# VCO_BFP420.net
KiCad netlist of a schematic drawn in Altium Designer
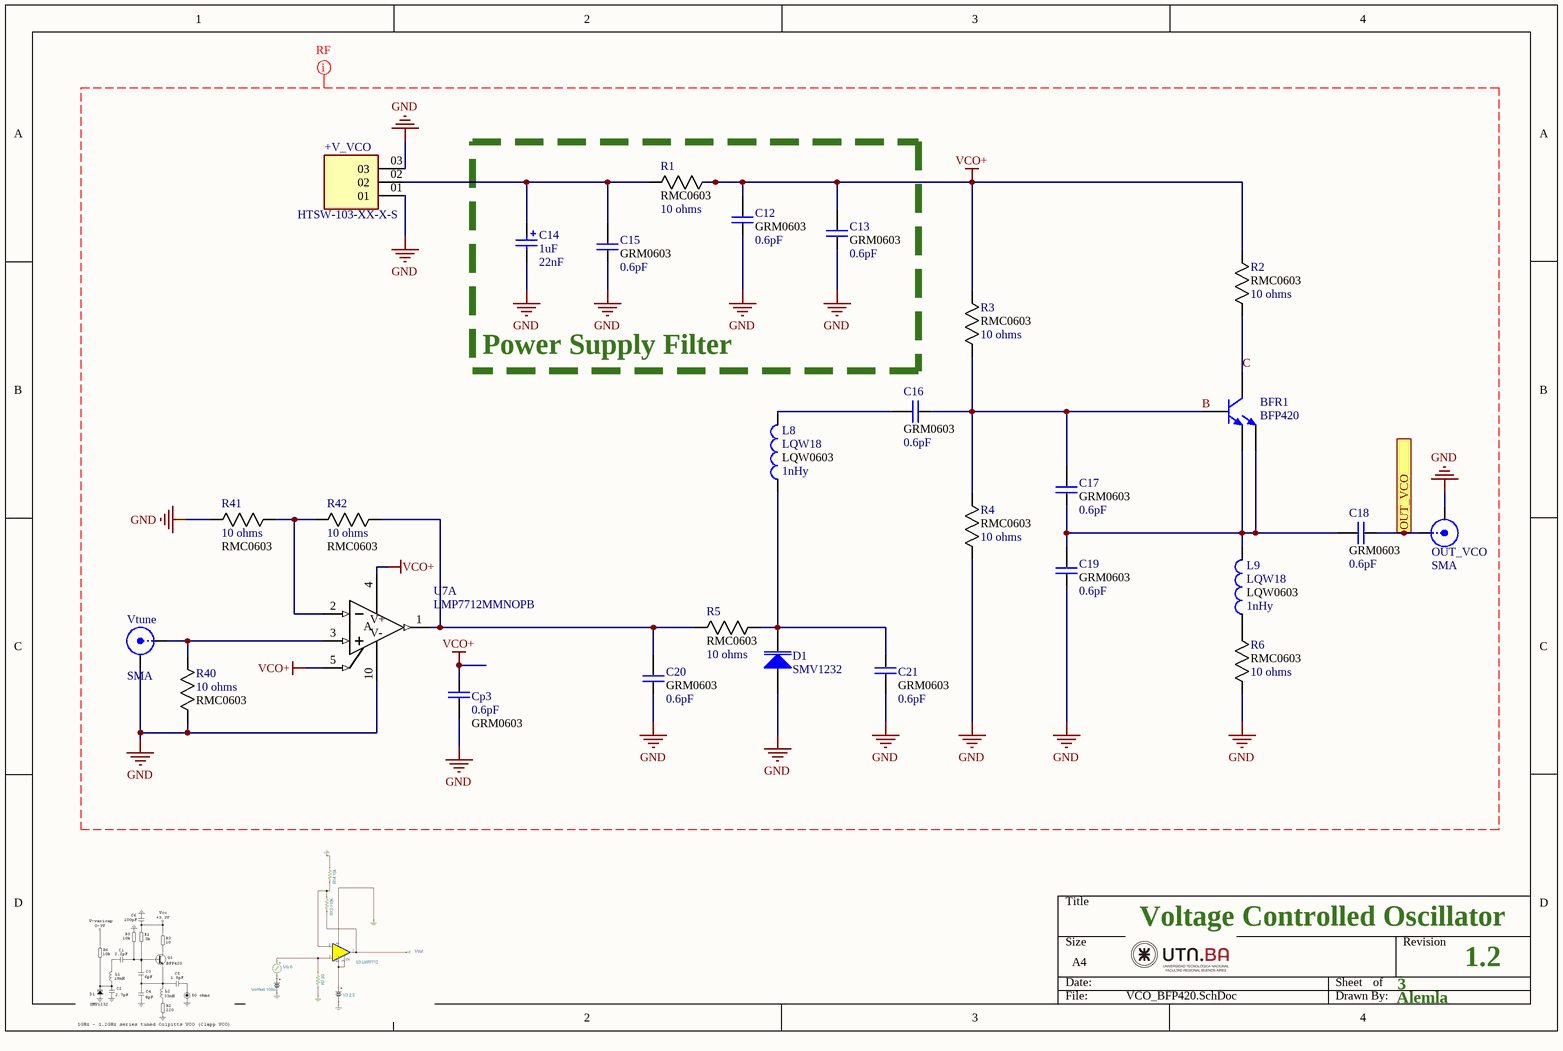
[diagram p0: VCO_BFP420.SchDoc]

(export (version "E")
  (design (tool "Eeschema 10.0.6"))
  (components
    (comp (ref "+V_VCO")
      (value "HTSW-103-XX-X-S")
      (footprint "SAMTEC_HTSW-103-XX-X-S")
      (description "Conn Unshrouded Header HDR 3 POS 2.54mm Solder ST Top Entry Thru-Hole Bag")
      (fields (field (name "MP") "HTSW-103-08-S-S") (field (name "MF") "Samtec"))
      (libsource (lib "HTSW-103-XX-X-S") (part "HTSW-103-XX-X-S"))
    )
    (comp (ref "BFR1")
      (value "BFP420")
      (footprint "SOT-343_N")
      (description "NPN Bipolar Transistor")
      (fields (field (name "PUBLISHER") "Altium Limited"))
      (libsource (lib "PCB_Project") (part "BFR460"))
    )
    (comp (ref "C12")
      (value "0.6pF")
      (footprint "GRM0603")
      (description "Capacitor GRM18 0603")
      (fields (field (name "Comment") "Cap 0603") (field (name "PUBLISHER") "Altium Limited"))
      (libsource (lib "Radar_RF_EAIII") (part "Cap"))
    )
    (comp (ref "C13")
      (value "0.6pF")
      (footprint "GRM0603")
      (description "Capacitor GRM18 0603")
      (fields (field (name "Comment") "Cap 0603") (field (name "PUBLISHER") "Altium Limited"))
      (libsource (lib "Radar_RF_EAIII") (part "Cap"))
    )
    (comp (ref "C14")
      (value "1uF")
      (footprint "6-0805_N")
      (description "Polarized Capacitor (Axial)")
      (fields (field (name "ALTIUM_VALUE") "22nF") (field (name "PUBLISHER") "Altium Limited"))
      (libsource (lib "PCB_Project") (part "Cap Pol2_1"))
    )
    (comp (ref "C15")
      (value "0.6pF")
      (footprint "GRM0603")
      (description "Capacitor GRM18 0603")
      (fields (field (name "Comment") "Cap 0603") (field (name "PUBLISHER") "Altium Limited"))
      (libsource (lib "Radar_RF_EAIII") (part "Cap"))
    )
    (comp (ref "C16")
      (value "0.6pF")
      (footprint "GRM0603")
      (description "Capacitor GRM18 0603")
      (fields (field (name "Comment") "Cap 0603") (field (name "PUBLISHER") "Altium Limited"))
      (libsource (lib "Radar_RF_EAIII") (part "Cap"))
    )
    (comp (ref "C17")
      (value "0.6pF")
      (footprint "GRM0603")
      (description "Capacitor GRM18 0603")
      (fields (field (name "Comment") "Cap 0603") (field (name "PUBLISHER") "Altium Limited"))
      (libsource (lib "Radar_RF_EAIII") (part "Cap"))
    )
    (comp (ref "C18")
      (value "0.6pF")
      (footprint "GRM0603")
      (description "Capacitor GRM18 0603")
      (fields (field (name "Comment") "Cap 0603") (field (name "PUBLISHER") "Altium Limited"))
      (libsource (lib "Radar_RF_EAIII") (part "Cap"))
    )
    (comp (ref "C19")
      (value "0.6pF")
      (footprint "GRM0603")
      (description "Capacitor GRM18 0603")
      (fields (field (name "Comment") "Cap 0603") (field (name "PUBLISHER") "Altium Limited"))
      (libsource (lib "Radar_RF_EAIII") (part "Cap"))
    )
    (comp (ref "C20")
      (value "0.6pF")
      (footprint "GRM0603")
      (description "Capacitor GRM18 0603")
      (fields (field (name "Comment") "Cap 0603") (field (name "PUBLISHER") "Altium Limited"))
      (libsource (lib "Radar_RF_EAIII") (part "Cap"))
    )
    (comp (ref "C21")
      (value "0.6pF")
      (footprint "GRM0603")
      (description "Capacitor GRM18 0603")
      (fields (field (name "Comment") "Cap 0603") (field (name "PUBLISHER") "Altium Limited"))
      (libsource (lib "Radar_RF_EAIII") (part "Cap"))
    )
    (comp (ref "Cp3")
      (value "0.6pF")
      (footprint "GRM0603")
      (description "Capacitor GRM18 0603")
      (fields (field (name "Comment") "Cap 0603") (field (name "PUBLISHER") "Altium Limited"))
      (libsource (lib "Lib_simb_Radar") (part "Cap"))
    )
    (comp (ref "D1")
      (value "SMV1232")
      (footprint "6-0805_N")
      (description "Variable Capacitance Diode")
      (fields (field (name "PUBLISHER") "Altium Limited"))
      (libsource (lib "Radar_RF_EAIII") (part "D Varactor"))
    )
    (comp (ref "L8")
      (value "LQW18")
      (footprint "INDC1608X100N")
      (description "Ind RF Chip Wirewound 18nH 5% 100MHz 40Q-Factor 550mA 0603 Paper T/R")
      (fields
        (field (name "MP") "LQW18AN18NJ00D")
        (field (name "PARAMETER 1") "LQW0603")
        (field (name "ALTIUM_VALUE") "1nHy")
      )
      (libsource (lib "Radar_RF_EAIII") (part "LQW18"))
    )
    (comp (ref "L9")
      (value "LQW18")
      (footprint "INDC1608X100N")
      (description "Ind RF Chip Wirewound 18nH 5% 100MHz 40Q-Factor 550mA 0603 Paper T/R")
      (fields
        (field (name "MP") "LQW18AN18NJ00D")
        (field (name "PARAMETER 1") "LQW0603")
        (field (name "ALTIUM_VALUE") "1nHy")
      )
      (libsource (lib "Radar_RF_EAIII") (part "LQW18"))
    )
    (comp (ref "OUT_VCO")
      (value "SMA")
      (footprint "SMA-142-0701-851_V2")
      (description "SMA Straight Connector")
      (fields (field (name "PUBLISHER") "Altium Limited"))
      (libsource (lib "Radar_RF_EAIII") (part "SMA"))
    )
    (comp (ref "R1")
      (value "10 ohms")
      (footprint "RMC0603")
      (description "Resistor RMC0603")
      (fields (field (name "Comment") "Resistor"))
      (libsource (lib "Radar_RF_EAIII") (part "Resistor"))
    )
    (comp (ref "R2")
      (value "10 ohms")
      (footprint "RMC0603")
      (description "Resistor RMC0603")
      (fields (field (name "Comment") "Resistor"))
      (libsource (lib "Radar_RF_EAIII") (part "Resistor"))
    )
    (comp (ref "R3")
      (value "10 ohms")
      (footprint "RMC0603")
      (description "Resistor RMC0603")
      (fields (field (name "Comment") "Resistor"))
      (libsource (lib "Radar_RF_EAIII") (part "Resistor"))
    )
    (comp (ref "R4")
      (value "10 ohms")
      (footprint "RMC0603")
      (description "Resistor RMC0603")
      (fields (field (name "Comment") "Resistor"))
      (libsource (lib "Radar_RF_EAIII") (part "Resistor"))
    )
    (comp (ref "R5")
      (value "10 ohms")
      (footprint "RMC0603")
      (description "Resistor RMC0603")
      (fields (field (name "Comment") "Resistor"))
      (libsource (lib "Radar_RF_EAIII") (part "Resistor"))
    )
    (comp (ref "R6")
      (value "10 ohms")
      (footprint "RMC0603")
      (description "Resistor RMC0603")
      (fields (field (name "Comment") "Resistor"))
      (libsource (lib "Radar_RF_EAIII") (part "Resistor"))
    )
    (comp (ref "R40")
      (value "10 ohms")
      (footprint "RMC0603")
      (description "Resistor RMC0603")
      (fields (field (name "Comment") "Resistor"))
      (libsource (lib "Lib_simb_Radar") (part "Resistor"))
    )
    (comp (ref "R41")
      (value "10 ohms")
      (footprint "RMC0603")
      (description "Resistor RMC0603")
      (fields (field (name "Comment") "Resistor"))
      (libsource (lib "Lib_simb_Radar") (part "Resistor"))
    )
    (comp (ref "R42")
      (value "10 ohms")
      (footprint "RMC0603")
      (description "Resistor RMC0603")
      (fields (field (name "Comment") "Resistor"))
      (libsource (lib "Lib_simb_Radar") (part "Resistor"))
    )
    (comp (ref "U7")
      (value "LMP7712MMNOPB")
      (footprint "SOP50P490X110-10N")
      (description "No Description Available")
      (fields
        (field (name "PARTNUMBER") "LMP7712MM")
        (field (name "MANUFACTURER") "NationalSemiconductor")
        (field (name "PUBLISHER") "NationalSemiconductor")
      )
      (libsource (lib "Lib_simb_Radar") (part "LMP7712MMNOPB"))
    )
    (comp (ref "Vtune")
      (value "SMA")
      (footprint "SMA-142-0701-851_V2")
      (description "SMA Straight Connector")
      (fields (field (name "PUBLISHER") "Altium Limited"))
      (libsource (lib "Radar_RF_EAIII") (part "SMA"))
    )
  )
  (nets
    (net (code "1") (name "/B") (class "Default")
      (node (ref "BFR1") (pin "4") (pinfunction "B_4") (pintype "passive"))
      (node (ref "C16") (pin "1") (pinfunction "1_1") (pintype "passive"))
      (node (ref "C17") (pin "2") (pinfunction "2_2") (pintype "passive"))
      (node (ref "R3") (pin "1") (pinfunction "1_1") (pintype "passive"))
      (node (ref "R4") (pin "2") (pinfunction "2_2") (pintype "passive"))
    )
    (net (code "2") (name "/C") (class "Default")
      (node (ref "BFR1") (pin "2") (pinfunction "C_2") (pintype "passive"))
      (node (ref "R2") (pin "1") (pinfunction "1_1") (pintype "passive"))
    )
    (net (code "3") (name "/OUT_VCO") (class "Default")
      (node (ref "C18") (pin "1") (pinfunction "1_1") (pintype "passive"))
      (node (ref "OUT_VCO") (pin "1") (pinfunction "X_1") (pintype "passive"))
    )
    (net (code "4") (name "GND") (class "Default")
      (node (ref "+V_VCO") (pin "01") (pinfunction "01_01") (pintype "passive"))
      (node (ref "+V_VCO") (pin "03") (pinfunction "03_03") (pintype "passive"))
      (node (ref "C12") (pin "1") (pinfunction "1_1") (pintype "passive"))
      (node (ref "C13") (pin "1") (pinfunction "1_1") (pintype "passive"))
      (node (ref "C14") (pin "2") (pinfunction "2_2") (pintype "passive"))
      (node (ref "C15") (pin "1") (pinfunction "1_1") (pintype "passive"))
      (node (ref "C19") (pin "1") (pinfunction "1_1") (pintype "passive"))
      (node (ref "C20") (pin "1") (pinfunction "1_1") (pintype "passive"))
      (node (ref "C21") (pin "2") (pinfunction "2_2") (pintype "passive"))
      (node (ref "Cp3") (pin "2") (pinfunction "2_2") (pintype "passive"))
      (node (ref "D1") (pin "1") (pinfunction "A_1") (pintype "passive"))
      (node (ref "OUT_VCO") (pin "2") (pinfunction "Y_2") (pintype "passive"))
      (node (ref "R4") (pin "1") (pinfunction "1_1") (pintype "passive"))
      (node (ref "R40") (pin "1") (pinfunction "1_1") (pintype "passive"))
      (node (ref "R41") (pin "1") (pinfunction "1_1") (pintype "passive"))
      (node (ref "R6") (pin "1") (pinfunction "1_1") (pintype "passive"))
      (node (ref "U7") (pin "10") (pinfunction "V+_10") (pintype "power_in"))
      (node (ref "Vtune") (pin "2") (pinfunction "Y_2") (pintype "passive"))
    )
    (net (code "5") (name "Net-(+V_VCO-Pad02)") (class "Default")
      (node (ref "+V_VCO") (pin "02") (pinfunction "02_02") (pintype "passive"))
      (node (ref "C14") (pin "1") (pinfunction "1_1") (pintype "passive"))
      (node (ref "C15") (pin "2") (pinfunction "2_2") (pintype "passive"))
      (node (ref "R1") (pin "1") (pinfunction "1_1") (pintype "passive"))
    )
    (net (code "6") (name "Net-(BFR1-E-Pad1)") (class "Default")
      (node (ref "BFR1") (pin "1") (pinfunction "E_1") (pintype "passive"))
      (node (ref "BFR1") (pin "3") (pinfunction "E_3") (pintype "passive"))
      (node (ref "C17") (pin "1") (pinfunction "1_1") (pintype "passive"))
      (node (ref "C18") (pin "2") (pinfunction "2_2") (pintype "passive"))
      (node (ref "C19") (pin "2") (pinfunction "2_2") (pintype "passive"))
      (node (ref "L9") (pin "2") (pinfunction "2_2") (pintype "passive"))
    )
    (net (code "7") (name "Net-(C16-Pad2)") (class "Default")
      (node (ref "C16") (pin "2") (pinfunction "2_2") (pintype "passive"))
      (node (ref "L8") (pin "2") (pinfunction "2_2") (pintype "passive"))
    )
    (net (code "8") (name "Net-(D1-K)") (class "Default")
      (node (ref "C21") (pin "1") (pinfunction "1_1") (pintype "passive"))
      (node (ref "D1") (pin "2") (pinfunction "K_2") (pintype "passive"))
      (node (ref "L8") (pin "1") (pinfunction "1_1") (pintype "passive"))
      (node (ref "R5") (pin "1") (pinfunction "1_1") (pintype "passive"))
    )
    (net (code "9") (name "Net-(L9-Pad1)") (class "Default")
      (node (ref "L9") (pin "1") (pinfunction "1_1") (pintype "passive"))
      (node (ref "R6") (pin "2") (pinfunction "2_2") (pintype "passive"))
    )
    (net (code "10") (name "Net-(U7A-IN+)") (class "Default")
      (node (ref "R40") (pin "2") (pinfunction "2_2") (pintype "passive"))
      (node (ref "U7") (pin "3") (pinfunction "IN+_3") (pintype "input"))
      (node (ref "Vtune") (pin "1") (pinfunction "X_1") (pintype "passive"))
    )
    (net (code "11") (name "Net-(U7A-IN-)") (class "Default")
      (node (ref "R41") (pin "2") (pinfunction "2_2") (pintype "passive"))
      (node (ref "R42") (pin "1") (pinfunction "1_1") (pintype "passive"))
      (node (ref "U7") (pin "2") (pinfunction "IN-_2") (pintype "input"))
    )
    (net (code "12") (name "Net-(U7A-OUT)") (class "Default")
      (node (ref "C20") (pin "2") (pinfunction "2_2") (pintype "passive"))
      (node (ref "R42") (pin "2") (pinfunction "2_2") (pintype "passive"))
      (node (ref "R5") (pin "2") (pinfunction "2_2") (pintype "passive"))
      (node (ref "U7") (pin "1") (pinfunction "OUT_1") (pintype "output"))
    )
    (net (code "13") (name "VCO+") (class "Default")
      (node (ref "C12") (pin "2") (pinfunction "2_2") (pintype "passive"))
      (node (ref "C13") (pin "2") (pinfunction "2_2") (pintype "passive"))
      (node (ref "Cp3") (pin "1") (pinfunction "1_1") (pintype "passive"))
      (node (ref "R1") (pin "2") (pinfunction "2_2") (pintype "passive"))
      (node (ref "R2") (pin "2") (pinfunction "2_2") (pintype "passive"))
      (node (ref "R3") (pin "2") (pinfunction "2_2") (pintype "passive"))
      (node (ref "U7") (pin "4") (pinfunction "V-_4") (pintype "power_in"))
      (node (ref "U7") (pin "5") (pinfunction "SD1_5") (pintype "input"))
    )
  )
)
